# NNP-DWG-125-001-000_PG4_Schematic_Drawin.net
KiCad netlist of a schematic drawn in Altium Designer
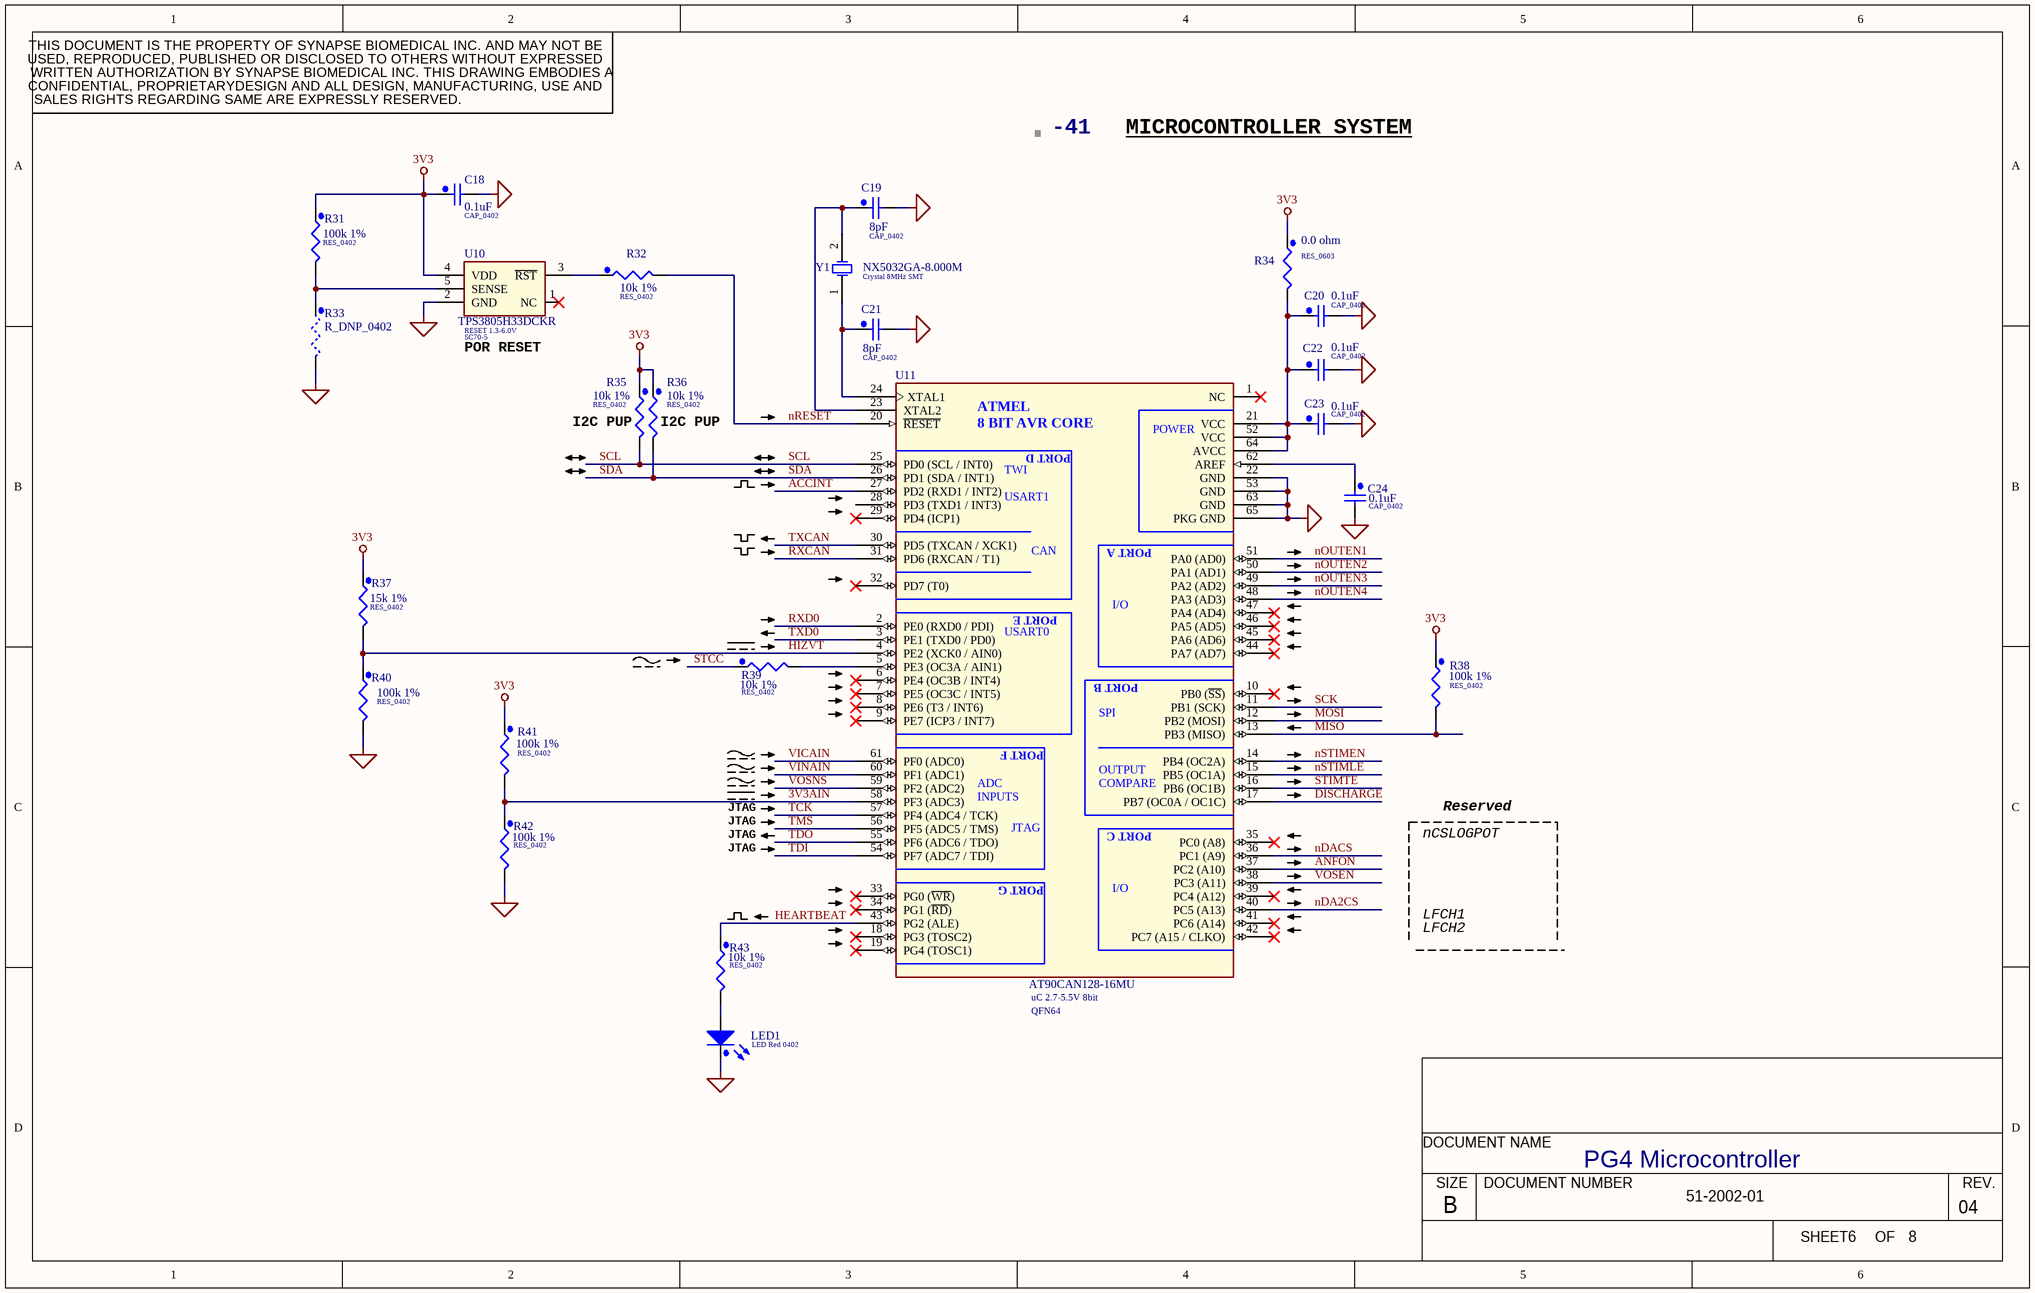
[diagram p0: NNP-DWG-125-001-000 PG4 Schematic Drawing Pg6.SchDoc]

(export (version "E")
  (design (tool "Eeschema 10.0.6"))
  (components
    (comp (ref "-41")
      (value "BOM_S1")
      (description "BOM item small graphic")
      (fields (field (name "XDESCRIPTION") "MICROCONTROLLER SYSTEM"))
      (libsource (lib "BOM_sym") (part "BOM_S1"))
    )
    (comp (ref "C18")
      (value "0.1uF")
      (footprint "CAP_0402")
      (description "0.1uF, 16V, X7R, 0402, RoHS")
      (fields
        (field (name "MFR") "Murata Electronics North America")
        (field (name "PACKAGEDESCRIPTION") "CAP_0402")
        (field (name "MPN") "GRM155R71C104KA88D")
      )
      (libsource (lib "NNPS Integrated Parts") (part "GRM155R71C104KA88D"))
    )
    (comp (ref "C19")
      (value "8pF")
      (footprint "CAP_0402")
      (description "8pF, 50V, C0G, 0402, 10%, RoHS")
      (fields
        (field (name "MFR") "Murata Electronics North America")
        (field (name "PACKAGEDESCRIPTION") "CAP_0402")
        (field (name "MPN") "GRM1555C1H8R0DA01D")
      )
      (libsource (lib "NNPS Integrated Parts") (part "ECJ-0EC1H080D"))
    )
    (comp (ref "C20")
      (value "0.1uF")
      (footprint "CAP_0402")
      (description "0.1uF, 16V, X7R, 0402, RoHS")
      (fields
        (field (name "MFR") "Murata Electronics North America")
        (field (name "PACKAGEDESCRIPTION") "CAP_0402")
        (field (name "MPN") "GRM155R71C104KA88D")
      )
      (libsource (lib "NNPS Integrated Parts") (part "GRM155R71C104KA88D"))
    )
    (comp (ref "C21")
      (value "8pF")
      (footprint "CAP_0402")
      (description "8pF, 50V, C0G, 0402, 10%, RoHS")
      (fields
        (field (name "MFR") "Murata Electronics North America")
        (field (name "PACKAGEDESCRIPTION") "CAP_0402")
        (field (name "MPN") "GRM1555C1H8R0DA01D")
      )
      (libsource (lib "NNPS Integrated Parts") (part "ECJ-0EC1H080D"))
    )
    (comp (ref "C22")
      (value "0.1uF")
      (footprint "CAP_0402")
      (description "0.1uF, 16V, X7R, 0402, RoHS")
      (fields
        (field (name "MFR") "Murata Electronics North America")
        (field (name "PACKAGEDESCRIPTION") "CAP_0402")
        (field (name "MPN") "GRM155R71C104KA88D")
      )
      (libsource (lib "NNPS Integrated Parts") (part "GRM155R71C104KA88D"))
    )
    (comp (ref "C23")
      (value "0.1uF")
      (footprint "CAP_0402")
      (description "0.1uF, 16V, X7R, 0402, RoHS")
      (fields
        (field (name "MFR") "Murata Electronics North America")
        (field (name "PACKAGEDESCRIPTION") "CAP_0402")
        (field (name "MPN") "GRM155R71C104KA88D")
      )
      (libsource (lib "NNPS Integrated Parts") (part "GRM155R71C104KA88D"))
    )
    (comp (ref "C24")
      (value "0.1uF")
      (footprint "CAP_0402")
      (description "0.1uF, 16V, X7R, 0402, RoHS")
      (fields
        (field (name "MFR") "Murata Electronics North America")
        (field (name "PACKAGEDESCRIPTION") "CAP_0402")
        (field (name "MPN") "GRM155R71C104KA88D")
      )
      (libsource (lib "NNPS Integrated Parts") (part "GRM155R71C104KA88D"))
    )
    (comp (ref "LED1")
      (value "LED Red 0402")
      (footprint "LED_0402_RED")
      (description "LED, Red, 0402, 20mA ,2V, 140mcd, RoHS")
      (fields (field (name "MFR") "Lumex Opto/Components Inc.") (field (name "MPN") "SML-LX0402SIC-TR"))
      (libsource (lib "NNPS Integrated Parts") (part "SML-LX0402SIC-TR"))
    )
    (comp (ref "R31")
      (value "100k 1%")
      (footprint "RES_0402")
      (description "100k ohm, 1%, 1/16W, smd, 0402, RoHS")
      (fields
        (field (name "MFR") "Vishay Dale")
        (field (name "PACKAGEDESCRIPTION") "RES_0402")
        (field (name "MPN") "CRCW04025K10FKED")
      )
      (libsource (lib "NNPS Integrated Parts") (part "MCR01MZPF1003"))
    )
    (comp (ref "R32")
      (value "10k 1%")
      (footprint "RES_0402")
      (description "10.0k ohm, 1%, 1/16W, smd, 0402, RoHS")
      (fields
        (field (name "MFR") "Vishay Dale")
        (field (name "PACKAGEDESCRIPTION") "RES_0402")
        (field (name "MPN") "CRCW040210K0FKED")
      )
      (libsource (lib "NNPS Integrated Parts") (part "MCR01MZPF1002"))
    )
    (comp (ref "R33")
      (value "R_DNP_0402")
      (footprint "RES_0402")
      (description "0.0 ohm 1/16W smd 0402 RoHS")
      (fields (field (name "MFR") "DO NOT POPULATE"))
      (libsource (lib "NNPS Integrated Parts") (part "R_DNP_0402"))
    )
    (comp (ref "R34")
      (value "0.0 ohm")
      (footprint "RES_0603")
      (description "0.0 ohm, 1/10W, 0603, RoHS")
      (fields
        (field (name "MFR") "Vishay Dale")
        (field (name "PACKAGEDESCRIPTION") "RES_0603")
        (field (name "MPN") "MCR03ERTJ000")
      )
      (libsource (lib "NNPS Integrated Parts") (part "MCR03ERTJ000"))
    )
    (comp (ref "R35")
      (value "10k 1%")
      (footprint "RES_0402")
      (description "10.0k ohm, 1%, 1/16W, smd, 0402, RoHS")
      (fields
        (field (name "MFR") "Vishay Dale")
        (field (name "PACKAGEDESCRIPTION") "RES_0402")
        (field (name "MPN") "CRCW040210K0FKED")
      )
      (libsource (lib "NNPS Integrated Parts") (part "MCR01MZPF1002"))
    )
    (comp (ref "R36")
      (value "10k 1%")
      (footprint "RES_0402")
      (description "10.0k ohm, 1%, 1/16W, smd, 0402, RoHS")
      (fields
        (field (name "MFR") "Vishay Dale")
        (field (name "PACKAGEDESCRIPTION") "RES_0402")
        (field (name "MPN") "CRCW040210K0FKED")
      )
      (libsource (lib "NNPS Integrated Parts") (part "MCR01MZPF1002"))
    )
    (comp (ref "R37")
      (value "15k 1%")
      (footprint "RES_0402")
      (description "15.0k ohm, 1%, 1/16W, smd, 0402, RoHS")
      (fields
        (field (name "MFR") "Vishay Dale")
        (field (name "PACKAGEDESCRIPTION") "RES_0402")
        (field (name "MPN") "CRCW040215K0FKED")
      )
      (libsource (lib "NNPS Integrated Parts") (part "MCR01MZPF1502"))
    )
    (comp (ref "R38")
      (value "100k 1%")
      (footprint "RES_0402")
      (description "100k ohm, 1%, 1/16W, smd, 0402, RoHS")
      (fields
        (field (name "MFR") "Vishay Dale")
        (field (name "PACKAGEDESCRIPTION") "RES_0402")
        (field (name "MPN") "CRCW04025K10FKED")
      )
      (libsource (lib "NNPS Integrated Parts") (part "MCR01MZPF1003"))
    )
    (comp (ref "R39")
      (value "10k 1%")
      (footprint "RES_0402")
      (description "10.0k ohm, 1%, 1/16W, smd, 0402, RoHS")
      (fields
        (field (name "MFR") "Vishay Dale")
        (field (name "PACKAGEDESCRIPTION") "RES_0402")
        (field (name "MPN") "CRCW040210K0FKED")
      )
      (libsource (lib "NNPS Integrated Parts") (part "MCR01MZPF1002"))
    )
    (comp (ref "R40")
      (value "100k 1%")
      (footprint "RES_0402")
      (description "100k ohm, 1%, 1/16W, smd, 0402, RoHS")
      (fields
        (field (name "MFR") "Vishay Dale")
        (field (name "PACKAGEDESCRIPTION") "RES_0402")
        (field (name "MPN") "CRCW04025K10FKED")
      )
      (libsource (lib "NNPS Integrated Parts") (part "MCR01MZPF1003"))
    )
    (comp (ref "R41")
      (value "100k 1%")
      (footprint "RES_0402")
      (description "100k ohm, 1%, 1/16W, smd, 0402, RoHS")
      (fields
        (field (name "MFR") "Vishay Dale")
        (field (name "PACKAGEDESCRIPTION") "RES_0402")
        (field (name "MPN") "CRCW04025K10FKED")
      )
      (libsource (lib "NNPS Integrated Parts") (part "MCR01MZPF1003"))
    )
    (comp (ref "R42")
      (value "100k 1%")
      (footprint "RES_0402")
      (description "100k ohm, 1%, 1/16W, smd, 0402, RoHS")
      (fields
        (field (name "MFR") "Vishay Dale")
        (field (name "PACKAGEDESCRIPTION") "RES_0402")
        (field (name "MPN") "CRCW04025K10FKED")
      )
      (libsource (lib "NNPS Integrated Parts") (part "MCR01MZPF1003"))
    )
    (comp (ref "R43")
      (value "10k 1%")
      (footprint "RES_0402")
      (description "10.0k ohm, 1%, 1/16W, smd, 0402, RoHS")
      (fields
        (field (name "MFR") "Vishay Dale")
        (field (name "PACKAGEDESCRIPTION") "RES_0402")
        (field (name "MPN") "CRCW040210K0FKED")
      )
      (libsource (lib "NNPS Integrated Parts") (part "MCR01MZPF1002"))
    )
    (comp (ref "U10")
      (value "RESET 1.3-6.0V")
      (footprint "SC70-5")
      (description "Voltage detector Reset, SC70-5, RoHS")
      (fields
        (field (name "MFR") "Texas Instruments")
        (field (name "PACKAGEDESCRIPTION") "SC70-5")
        (field (name "MPN") "TPS3805H33DCKR")
      )
      (libsource (lib "NNPS Integrated Parts") (part "TPS3805H33"))
    )
    (comp (ref "U11")
      (value "uC 2.7-5.5V 8bit")
      (footprint "QFN64")
      (description "uC, 2.7-5.5V, 8bit, QFN64, RoHS")
      (fields
        (field (name "MFR") "Atmel")
        (field (name "PACKAGEDESCRIPTION") "QFN64")
        (field (name "MPN") "AT90CAN128-16MU")
      )
      (libsource (lib "NNPS Integrated Parts") (part "AT90CAN128-16MI"))
    )
    (comp (ref "Y1")
      (value "Crystal 8MHz SMT")
      (footprint "NX5032GA")
      (description "Crystal 8MHz SMT, RoHS")
      (fields (field (name "MFR") "NDK") (field (name "MPN") "NX5032GA-8.000M"))
      (libsource (lib "NNPS Integrated Parts") (part "NX5032GA"))
    )
  )
  (nets
    (net (code "1") (name "/3V3AIN") (class "Default")
      (node (ref "R41") (pin "2") (pinfunction "2_2") (pintype "passive"))
      (node (ref "R42") (pin "1") (pinfunction "1_1") (pintype "passive"))
      (node (ref "U11") (pin "58") (pinfunction "PF3_(ADC3)_58") (pintype "bidirectional"))
    )
    (net (code "2") (name "/ACCINT") (class "Default")
      (node (ref "U11") (pin "27") (pinfunction "PD2_(RXD1_/_INT2)_27") (pintype "bidirectional"))
    )
    (net (code "3") (name "/ANFON") (class "Default")
      (node (ref "U11") (pin "37") (pinfunction "PC2_(A10)_37") (pintype "bidirectional"))
    )
    (net (code "4") (name "/DISCHARGE") (class "Default")
      (node (ref "U11") (pin "17") (pinfunction "PB7_(OC0A_/_OC1C)_17") (pintype "bidirectional"))
    )
    (net (code "5") (name "/HEARTBEAT") (class "Default")
      (node (ref "R43") (pin "1") (pinfunction "1_1") (pintype "passive"))
      (node (ref "U11") (pin "43") (pinfunction "PG2_(ALE)_43") (pintype "bidirectional"))
    )
    (net (code "6") (name "/HIZVT") (class "Default")
      (node (ref "R37") (pin "2") (pinfunction "2_2") (pintype "passive"))
      (node (ref "R40") (pin "1") (pinfunction "1_1") (pintype "passive"))
      (node (ref "U11") (pin "4") (pinfunction "PE2_(XCK0_/_AIN0)_4") (pintype "bidirectional"))
    )
    (net (code "7") (name "/MISO") (class "Default")
      (node (ref "R38") (pin "2") (pinfunction "2_2") (pintype "passive"))
      (node (ref "U11") (pin "13") (pinfunction "PB3_(MISO)_13") (pintype "bidirectional"))
    )
    (net (code "8") (name "/MOSI") (class "Default")
      (node (ref "U11") (pin "12") (pinfunction "PB2_(MOSI)_12") (pintype "bidirectional"))
    )
    (net (code "9") (name "/RXCAN") (class "Default")
      (node (ref "U11") (pin "31") (pinfunction "PD6_(RXCAN_/_T1)_31") (pintype "bidirectional"))
    )
    (net (code "10") (name "/RXD0") (class "Default")
      (node (ref "U11") (pin "2") (pinfunction "PE0_(RXD0_/_PDI)_2") (pintype "bidirectional"))
    )
    (net (code "11") (name "/SCK") (class "Default")
      (node (ref "U11") (pin "11") (pinfunction "PB1_(SCK)_11") (pintype "bidirectional"))
    )
    (net (code "12") (name "/SCL") (class "Default")
      (node (ref "R35") (pin "2") (pinfunction "2_2") (pintype "passive"))
      (node (ref "U11") (pin "25") (pinfunction "PD0_(SCL_/_INT0)_25") (pintype "bidirectional"))
    )
    (net (code "13") (name "/SDA") (class "Default")
      (node (ref "R36") (pin "2") (pinfunction "2_2") (pintype "passive"))
      (node (ref "U11") (pin "26") (pinfunction "PD1_(SDA_/_INT1)_26") (pintype "bidirectional"))
    )
    (net (code "14") (name "/STCC") (class "Default")
      (node (ref "R39") (pin "1") (pinfunction "1_1") (pintype "passive"))
    )
    (net (code "15") (name "/STIMTE") (class "Default")
      (node (ref "U11") (pin "16") (pinfunction "PB6_(OC1B)_16") (pintype "bidirectional"))
    )
    (net (code "16") (name "/TCK") (class "Default")
      (node (ref "U11") (pin "57") (pinfunction "PF4_(ADC4_/_TCK)_57") (pintype "bidirectional"))
    )
    (net (code "17") (name "/TDI") (class "Default")
      (node (ref "U11") (pin "54") (pinfunction "PF7_(ADC7_/_TDI)_54") (pintype "bidirectional"))
    )
    (net (code "18") (name "/TDO") (class "Default")
      (node (ref "U11") (pin "55") (pinfunction "PF6_(ADC6_/_TDO)_55") (pintype "bidirectional"))
    )
    (net (code "19") (name "/TMS") (class "Default")
      (node (ref "U11") (pin "56") (pinfunction "PF5_(ADC5_/_TMS)_56") (pintype "bidirectional"))
    )
    (net (code "20") (name "/TXCAN") (class "Default")
      (node (ref "U11") (pin "30") (pinfunction "PD5_(TXCAN_/_XCK1)_30") (pintype "bidirectional"))
    )
    (net (code "21") (name "/TXD0") (class "Default")
      (node (ref "U11") (pin "3") (pinfunction "PE1_(TXD0_/_PD0)_3") (pintype "bidirectional"))
    )
    (net (code "22") (name "/VICAIN") (class "Default")
      (node (ref "U11") (pin "61") (pinfunction "PF0_(ADC0)_61") (pintype "bidirectional"))
    )
    (net (code "23") (name "/VINAIN") (class "Default")
      (node (ref "U11") (pin "60") (pinfunction "PF1_(ADC1)_60") (pintype "bidirectional"))
    )
    (net (code "24") (name "/VOSEN") (class "Default")
      (node (ref "U11") (pin "38") (pinfunction "PC3_(A11)_38") (pintype "bidirectional"))
    )
    (net (code "25") (name "/VOSNS") (class "Default")
      (node (ref "U11") (pin "59") (pinfunction "PF2_(ADC2)_59") (pintype "bidirectional"))
    )
    (net (code "26") (name "/nDA2CS") (class "Default")
      (node (ref "U11") (pin "40") (pinfunction "PC5_(A13)_40") (pintype "bidirectional"))
    )
    (net (code "27") (name "/nDACS") (class "Default")
      (node (ref "U11") (pin "36") (pinfunction "PC1_(A9)_36") (pintype "bidirectional"))
    )
    (net (code "28") (name "/nOUTEN1") (class "Default")
      (node (ref "U11") (pin "51") (pinfunction "PA0_(AD0)_51") (pintype "bidirectional"))
    )
    (net (code "29") (name "/nOUTEN2") (class "Default")
      (node (ref "U11") (pin "50") (pinfunction "PA1_(AD1)_50") (pintype "bidirectional"))
    )
    (net (code "30") (name "/nOUTEN3") (class "Default")
      (node (ref "U11") (pin "49") (pinfunction "PA2_(AD2)_49") (pintype "bidirectional"))
    )
    (net (code "31") (name "/nOUTEN4") (class "Default")
      (node (ref "U11") (pin "48") (pinfunction "PA3_(AD3)_48") (pintype "bidirectional"))
    )
    (net (code "32") (name "/nRESET") (class "Default")
      (node (ref "R32") (pin "2") (pinfunction "2_2") (pintype "passive"))
      (node (ref "U11") (pin "20") (pinfunction "~{RESET}_20") (pintype "input"))
    )
    (net (code "33") (name "/nSTIMEN") (class "Default")
      (node (ref "U11") (pin "14") (pinfunction "PB4_(OC2A)_14") (pintype "bidirectional"))
    )
    (net (code "34") (name "/nSTIMLE") (class "Default")
      (node (ref "U11") (pin "15") (pinfunction "PB5_(OC1A)_15") (pintype "bidirectional"))
    )
    (net (code "35") (name "3V3") (class "Default")
      (node (ref "C18") (pin "1") (pinfunction "1_1") (pintype "passive"))
      (node (ref "R31") (pin "1") (pinfunction "1_1") (pintype "passive"))
      (node (ref "R34") (pin "1") (pinfunction "1_1") (pintype "passive"))
      (node (ref "R35") (pin "1") (pinfunction "1_1") (pintype "passive"))
      (node (ref "R36") (pin "1") (pinfunction "1_1") (pintype "passive"))
      (node (ref "R37") (pin "1") (pinfunction "1_1") (pintype "passive"))
      (node (ref "R38") (pin "1") (pinfunction "1_1") (pintype "passive"))
      (node (ref "R41") (pin "1") (pinfunction "1_1") (pintype "passive"))
      (node (ref "U10") (pin "4") (pinfunction "VDD_4") (pintype "passive"))
    )
    (net (code "36") (name "GND") (class "Default")
      (node (ref "C18") (pin "2") (pinfunction "2_2") (pintype "passive"))
      (node (ref "C19") (pin "2") (pinfunction "2_2") (pintype "passive"))
      (node (ref "C20") (pin "2") (pinfunction "2_2") (pintype "passive"))
      (node (ref "C21") (pin "2") (pinfunction "2_2") (pintype "passive"))
      (node (ref "C22") (pin "2") (pinfunction "2_2") (pintype "passive"))
      (node (ref "C23") (pin "2") (pinfunction "2_2") (pintype "passive"))
      (node (ref "C24") (pin "2") (pinfunction "2_2") (pintype "passive"))
      (node (ref "LED1") (pin "1") (pinfunction "C_1") (pintype "passive"))
      (node (ref "R33") (pin "2") (pinfunction "2_2") (pintype "passive"))
      (node (ref "R40") (pin "2") (pinfunction "2_2") (pintype "passive"))
      (node (ref "R42") (pin "2") (pinfunction "2_2") (pintype "passive"))
      (node (ref "U10") (pin "2") (pinfunction "GND_2") (pintype "passive"))
      (node (ref "U11") (pin "22") (pinfunction "GND_22") (pintype "power_in"))
      (node (ref "U11") (pin "53") (pinfunction "GND_53") (pintype "power_in"))
      (node (ref "U11") (pin "63") (pinfunction "GND_63") (pintype "power_in"))
      (node (ref "U11") (pin "65") (pinfunction "PKG_GND_65") (pintype "power_in"))
    )
    (net (code "37") (name "Net-(LED1-A)") (class "Default")
      (node (ref "LED1") (pin "2") (pinfunction "A_2") (pintype "passive"))
      (node (ref "R43") (pin "2") (pinfunction "2_2") (pintype "passive"))
    )
    (net (code "38") (name "Net-(U10-RST)") (class "Default")
      (node (ref "R32") (pin "1") (pinfunction "1_1") (pintype "passive"))
      (node (ref "U10") (pin "3") (pinfunction "RST_3") (pintype "passive"))
    )
    (net (code "39") (name "Net-(U10-SENSE)") (class "Default")
      (node (ref "R31") (pin "2") (pinfunction "2_2") (pintype "passive"))
      (node (ref "R33") (pin "1") (pinfunction "1_1") (pintype "passive"))
      (node (ref "U10") (pin "5") (pinfunction "SENSE_5") (pintype "passive"))
    )
    (net (code "40") (name "Net-(U11-AREF)") (class "Default")
      (node (ref "C24") (pin "1") (pinfunction "1_1") (pintype "passive"))
      (node (ref "U11") (pin "62") (pinfunction "AREF_62") (pintype "input"))
    )
    (net (code "41") (name "Net-(U11-AVCC)") (class "Default")
      (node (ref "C20") (pin "1") (pinfunction "1_1") (pintype "passive"))
      (node (ref "C22") (pin "1") (pinfunction "1_1") (pintype "passive"))
      (node (ref "C23") (pin "1") (pinfunction "1_1") (pintype "passive"))
      (node (ref "R34") (pin "2") (pinfunction "2_2") (pintype "passive"))
      (node (ref "U11") (pin "21") (pinfunction "VCC_21") (pintype "power_in"))
      (node (ref "U11") (pin "52") (pinfunction "VCC_52") (pintype "power_in"))
      (node (ref "U11") (pin "64") (pinfunction "AVCC_64") (pintype "power_in"))
    )
    (net (code "42") (name "Net-(U11-PE3_(OC3A_{slash}_AIN1))") (class "Default")
      (node (ref "R39") (pin "2") (pinfunction "2_2") (pintype "passive"))
      (node (ref "U11") (pin "5") (pinfunction "PE3_(OC3A_/_AIN1)_5") (pintype "bidirectional"))
    )
    (net (code "43") (name "Net-(U11-XTAL1)") (class "Default")
      (node (ref "C21") (pin "1") (pinfunction "1_1") (pintype "passive"))
      (node (ref "U11") (pin "24") (pinfunction "XTAL1_24") (pintype "passive"))
      (node (ref "Y1") (pin "1") (pinfunction "OSC1_1") (pintype "passive"))
    )
    (net (code "44") (name "Net-(U11-XTAL2)") (class "Default")
      (node (ref "C19") (pin "1") (pinfunction "1_1") (pintype "passive"))
      (node (ref "U11") (pin "23") (pinfunction "XTAL2_23") (pintype "passive"))
      (node (ref "Y1") (pin "2") (pinfunction "OSC2_2") (pintype "passive"))
    )
    (net (code "45") (name "unconnected-(U10-NC-Pad1)") (class "Default")
      (node (ref "U10") (pin "1") (pinfunction "NC_1") (pintype "passive+no_connect"))
    )
    (net (code "46") (name "unconnected-(U11-NC-Pad1)") (class "Default")
      (node (ref "U11") (pin "1") (pinfunction "NC_1") (pintype "passive+no_connect"))
    )
    (net (code "47") (name "unconnected-(U11-PA4_(AD4)-Pad47)") (class "Default")
      (node (ref "U11") (pin "47") (pinfunction "PA4_(AD4)_47") (pintype "bidirectional+no_connect"))
    )
    (net (code "48") (name "unconnected-(U11-PA5_(AD5)-Pad46)") (class "Default")
      (node (ref "U11") (pin "46") (pinfunction "PA5_(AD5)_46") (pintype "bidirectional+no_connect"))
    )
    (net (code "49") (name "unconnected-(U11-PA6_(AD6)-Pad45)") (class "Default")
      (node (ref "U11") (pin "45") (pinfunction "PA6_(AD6)_45") (pintype "bidirectional+no_connect"))
    )
    (net (code "50") (name "unconnected-(U11-PA7_(AD7)-Pad44)") (class "Default")
      (node (ref "U11") (pin "44") (pinfunction "PA7_(AD7)_44") (pintype "bidirectional+no_connect"))
    )
    (net (code "51") (name "unconnected-(U11-PB0_(~{SS})-Pad10)") (class "Default")
      (node (ref "U11") (pin "10") (pinfunction "PB0_(~{SS})_10") (pintype "bidirectional+no_connect"))
    )
    (net (code "52") (name "unconnected-(U11-PC0_(A8)-Pad35)") (class "Default")
      (node (ref "U11") (pin "35") (pinfunction "PC0_(A8)_35") (pintype "bidirectional+no_connect"))
    )
    (net (code "53") (name "unconnected-(U11-PC4_(A12)-Pad39)") (class "Default")
      (node (ref "U11") (pin "39") (pinfunction "PC4_(A12)_39") (pintype "bidirectional+no_connect"))
    )
    (net (code "54") (name "unconnected-(U11-PC6_(A14)-Pad41)") (class "Default")
      (node (ref "U11") (pin "41") (pinfunction "PC6_(A14)_41") (pintype "bidirectional+no_connect"))
    )
    (net (code "55") (name "unconnected-(U11-PC7_(A15_{slash}_CLKO)-Pad42)") (class "Default")
      (node (ref "U11") (pin "42") (pinfunction "PC7_(A15_/_CLKO)_42") (pintype "bidirectional+no_connect"))
    )
    (net (code "56") (name "unconnected-(U11-PD3_(TXD1_{slash}_INT3)-Pad28)") (class "Default")
      (node (ref "U11") (pin "28") (pinfunction "PD3_(TXD1_/_INT3)_28") (pintype "bidirectional"))
    )
    (net (code "57") (name "unconnected-(U11-PD4_(ICP1)-Pad29)") (class "Default")
      (node (ref "U11") (pin "29") (pinfunction "PD4_(ICP1)_29") (pintype "bidirectional+no_connect"))
    )
    (net (code "58") (name "unconnected-(U11-PD7_(T0)-Pad32)") (class "Default")
      (node (ref "U11") (pin "32") (pinfunction "PD7_(T0)_32") (pintype "bidirectional+no_connect"))
    )
    (net (code "59") (name "unconnected-(U11-PE4_(OC3B_{slash}_INT4)-Pad6)") (class "Default")
      (node (ref "U11") (pin "6") (pinfunction "PE4_(OC3B_/_INT4)_6") (pintype "bidirectional+no_connect"))
    )
    (net (code "60") (name "unconnected-(U11-PE5_(OC3C_{slash}_INT5)-Pad7)") (class "Default")
      (node (ref "U11") (pin "7") (pinfunction "PE5_(OC3C_/_INT5)_7") (pintype "bidirectional+no_connect"))
    )
    (net (code "61") (name "unconnected-(U11-PE6_(T3_{slash}_INT6)-Pad8)") (class "Default")
      (node (ref "U11") (pin "8") (pinfunction "PE6_(T3_/_INT6)_8") (pintype "bidirectional+no_connect"))
    )
    (net (code "62") (name "unconnected-(U11-PE7_(ICP3_{slash}_INT7)-Pad9)") (class "Default")
      (node (ref "U11") (pin "9") (pinfunction "PE7_(ICP3_/_INT7)_9") (pintype "bidirectional+no_connect"))
    )
    (net (code "63") (name "unconnected-(U11-PG0_(~{WR})-Pad33)") (class "Default")
      (node (ref "U11") (pin "33") (pinfunction "PG0_(~{WR})_33") (pintype "bidirectional+no_connect"))
    )
    (net (code "64") (name "unconnected-(U11-PG1_(~{RD})-Pad34)") (class "Default")
      (node (ref "U11") (pin "34") (pinfunction "PG1_(~{RD})_34") (pintype "bidirectional+no_connect"))
    )
    (net (code "65") (name "unconnected-(U11-PG3_(TOSC2)-Pad18)") (class "Default")
      (node (ref "U11") (pin "18") (pinfunction "PG3_(TOSC2)_18") (pintype "bidirectional+no_connect"))
    )
    (net (code "66") (name "unconnected-(U11-PG4_(TOSC1)-Pad19)") (class "Default")
      (node (ref "U11") (pin "19") (pinfunction "PG4_(TOSC1)_19") (pintype "bidirectional+no_connect"))
    )
  )
)
